# Sheet1.net
KiCad netlist of a schematic drawn in Altium Designer
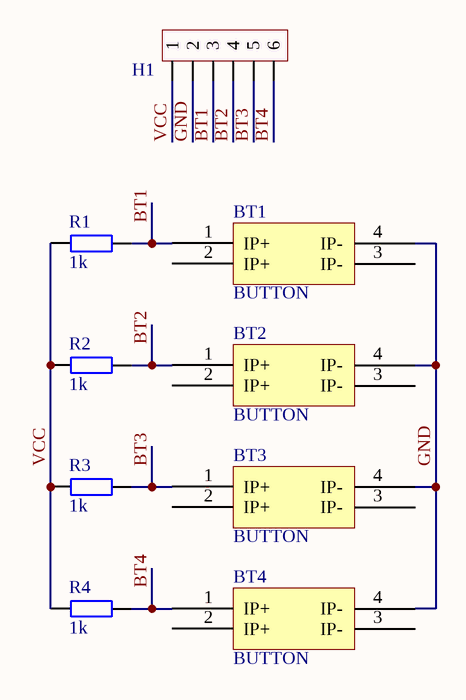
[diagram p0: Sheet1.SchDoc]

(export (version "E")
  (design (tool "Eeschema 10.0.6"))
  (components
    (comp (ref "BT1")
      (value "BUTTON")
      (footprint "BUTTON4")
      (libsource (lib "THU_VIEN_PQB_Schlib1") (part "BUTTON4"))
    )
    (comp (ref "BT2")
      (value "BUTTON")
      (footprint "BUTTON4")
      (libsource (lib "THU_VIEN_PQB_Schlib1") (part "BUTTON4"))
    )
    (comp (ref "BT3")
      (value "BUTTON")
      (footprint "BUTTON4")
      (libsource (lib "THU_VIEN_PQB_Schlib1") (part "BUTTON4"))
    )
    (comp (ref "BT4")
      (value "BUTTON")
      (footprint "BUTTON4")
      (libsource (lib "THU_VIEN_PQB_Schlib1") (part "BUTTON4"))
    )
    (comp (ref "H1")
      (value "Header6")
      (footprint "HDR6")
      (description "Header IDC, 6 x 1 Pin Vertical 2.54mm Pitch (Non-Boxed, Male)")
      (libsource (lib "LIBRARY") (part "Header6"))
    )
    (comp (ref "R1")
      (value "1k")
      (footprint "R1/4W")
      (description "Resistor 1/4W")
      (libsource (lib "syhaunguyen") (part "R1/4W"))
    )
    (comp (ref "R2")
      (value "1k")
      (footprint "R1/4W")
      (description "Resistor 1/4W")
      (libsource (lib "syhaunguyen") (part "R1/4W"))
    )
    (comp (ref "R3")
      (value "1k")
      (footprint "R1/4W")
      (description "Resistor 1/4W")
      (libsource (lib "syhaunguyen") (part "R1/4W"))
    )
    (comp (ref "R4")
      (value "1k")
      (footprint "R1/4W")
      (description "Resistor 1/4W")
      (libsource (lib "syhaunguyen") (part "R1/4W"))
    )
  )
  (nets
    (net (code "1") (name "/BT1") (class "Default")
      (node (ref "BT1") (pin "1") (pinfunction "IP+_1") (pintype "passive"))
      (node (ref "H1") (pin "3") (pinfunction "3_3") (pintype "passive"))
      (node (ref "R1") (pin "2") (pinfunction "2_2") (pintype "passive"))
    )
    (net (code "2") (name "/BT2") (class "Default")
      (node (ref "BT2") (pin "1") (pinfunction "IP+_1") (pintype "passive"))
      (node (ref "H1") (pin "4") (pinfunction "4_4") (pintype "passive"))
      (node (ref "R2") (pin "2") (pinfunction "2_2") (pintype "passive"))
    )
    (net (code "3") (name "/BT3") (class "Default")
      (node (ref "BT3") (pin "1") (pinfunction "IP+_1") (pintype "passive"))
      (node (ref "H1") (pin "5") (pinfunction "5_5") (pintype "passive"))
      (node (ref "R3") (pin "2") (pinfunction "2_2") (pintype "passive"))
    )
    (net (code "4") (name "/BT4") (class "Default")
      (node (ref "BT4") (pin "1") (pinfunction "IP+_1") (pintype "passive"))
      (node (ref "H1") (pin "6") (pinfunction "6_6") (pintype "passive"))
      (node (ref "R4") (pin "2") (pinfunction "2_2") (pintype "passive"))
    )
    (net (code "5") (name "/GND") (class "Default")
      (node (ref "BT1") (pin "4") (pinfunction "IP-_4") (pintype "passive"))
      (node (ref "BT2") (pin "4") (pinfunction "IP-_4") (pintype "passive"))
      (node (ref "BT3") (pin "4") (pinfunction "IP-_4") (pintype "passive"))
      (node (ref "BT4") (pin "4") (pinfunction "IP-_4") (pintype "passive"))
      (node (ref "H1") (pin "2") (pinfunction "2_2") (pintype "passive"))
    )
    (net (code "6") (name "/VCC") (class "Default")
      (node (ref "H1") (pin "1") (pinfunction "1_1") (pintype "passive"))
      (node (ref "R1") (pin "1") (pinfunction "1_1") (pintype "passive"))
      (node (ref "R2") (pin "1") (pinfunction "1_1") (pintype "passive"))
      (node (ref "R3") (pin "1") (pinfunction "1_1") (pintype "passive"))
      (node (ref "R4") (pin "1") (pinfunction "1_1") (pintype "passive"))
    )
    (net (code "7") (name "unconnected-(BT1-IP+-Pad2)") (class "Default")
      (node (ref "BT1") (pin "2") (pinfunction "IP+_2") (pintype "passive"))
    )
    (net (code "8") (name "unconnected-(BT1-IP--Pad3)") (class "Default")
      (node (ref "BT1") (pin "3") (pinfunction "IP-_3") (pintype "passive"))
    )
    (net (code "9") (name "unconnected-(BT2-IP+-Pad2)") (class "Default")
      (node (ref "BT2") (pin "2") (pinfunction "IP+_2") (pintype "passive"))
    )
    (net (code "10") (name "unconnected-(BT2-IP--Pad3)") (class "Default")
      (node (ref "BT2") (pin "3") (pinfunction "IP-_3") (pintype "passive"))
    )
    (net (code "11") (name "unconnected-(BT3-IP+-Pad2)") (class "Default")
      (node (ref "BT3") (pin "2") (pinfunction "IP+_2") (pintype "passive"))
    )
    (net (code "12") (name "unconnected-(BT3-IP--Pad3)") (class "Default")
      (node (ref "BT3") (pin "3") (pinfunction "IP-_3") (pintype "passive"))
    )
    (net (code "13") (name "unconnected-(BT4-IP+-Pad2)") (class "Default")
      (node (ref "BT4") (pin "2") (pinfunction "IP+_2") (pintype "passive"))
    )
    (net (code "14") (name "unconnected-(BT4-IP--Pad3)") (class "Default")
      (node (ref "BT4") (pin "3") (pinfunction "IP-_3") (pintype "passive"))
    )
  )
)
